# RT7258QW-break.net
KiCad netlist of a schematic drawn in EAGLE
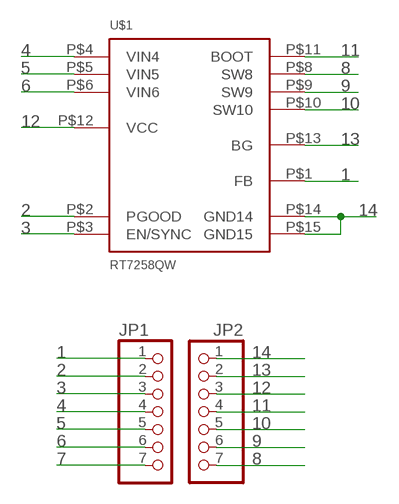
[diagram p0: schematic, sheet 1]

(export (version "E")
  (design (tool "Eeschema 10.0.6"))
  (components
    (comp (ref "JP1")
      (value "PINHD-1X7")
      (footprint "eagle-import:1X07")
      (libsource (lib "eagle-import") (part "PINHD-1X7"))
    )
    (comp (ref "JP2")
      (value "PINHD-1X7")
      (footprint "eagle-import:1X07")
      (libsource (lib "eagle-import") (part "PINHD-1X7"))
    )
    (comp (ref "U$1")
      (value "RT7258QW")
      (footprint "eagle-import:RT7258GQW")
      (libsource (lib "eagle-import") (part "RT7258QW"))
    )
  )
  (nets
    (net (code "1") (name "/1") (class "Default")
      (node (ref "JP1") (pin "1") (pinfunction "1_1") (pintype "passive"))
      (node (ref "U$1") (pin "P$1") (pinfunction "FB_P$1") (pintype "bidirectional"))
    )
    (net (code "2") (name "/2") (class "Default")
      (node (ref "JP1") (pin "2") (pinfunction "2_2") (pintype "passive"))
      (node (ref "U$1") (pin "P$2") (pinfunction "PGOOD_P$2") (pintype "bidirectional"))
    )
    (net (code "3") (name "/3") (class "Default")
      (node (ref "JP1") (pin "3") (pinfunction "3_3") (pintype "passive"))
      (node (ref "U$1") (pin "P$3") (pinfunction "EN/SYNC_P$3") (pintype "bidirectional"))
    )
    (net (code "4") (name "/4") (class "Default")
      (node (ref "JP1") (pin "4") (pinfunction "4_4") (pintype "passive"))
      (node (ref "U$1") (pin "P$4") (pinfunction "VIN4_P$4") (pintype "bidirectional"))
    )
    (net (code "5") (name "/5") (class "Default")
      (node (ref "JP1") (pin "5") (pinfunction "5_5") (pintype "passive"))
      (node (ref "U$1") (pin "P$5") (pinfunction "VIN5_P$5") (pintype "bidirectional"))
    )
    (net (code "6") (name "/6") (class "Default")
      (node (ref "JP1") (pin "6") (pinfunction "6_6") (pintype "passive"))
      (node (ref "U$1") (pin "P$6") (pinfunction "VIN6_P$6") (pintype "bidirectional"))
    )
    (net (code "7") (name "/7") (class "Default")
      (node (ref "JP1") (pin "7") (pinfunction "7_7") (pintype "passive"))
    )
    (net (code "8") (name "/8") (class "Default")
      (node (ref "JP2") (pin "7") (pinfunction "7_7") (pintype "passive"))
      (node (ref "U$1") (pin "P$8") (pinfunction "SW8_P$8") (pintype "bidirectional"))
    )
    (net (code "9") (name "/9") (class "Default")
      (node (ref "JP2") (pin "6") (pinfunction "6_6") (pintype "passive"))
      (node (ref "U$1") (pin "P$9") (pinfunction "SW9_P$9") (pintype "bidirectional"))
    )
    (net (code "10") (name "/10") (class "Default")
      (node (ref "JP2") (pin "5") (pinfunction "5_5") (pintype "passive"))
      (node (ref "U$1") (pin "P$10") (pinfunction "SW10_P$10") (pintype "bidirectional"))
    )
    (net (code "11") (name "/11") (class "Default")
      (node (ref "JP2") (pin "4") (pinfunction "4_4") (pintype "passive"))
      (node (ref "U$1") (pin "P$11") (pinfunction "BOOT_P$11") (pintype "bidirectional"))
    )
    (net (code "12") (name "/12") (class "Default")
      (node (ref "JP2") (pin "3") (pinfunction "3_3") (pintype "passive"))
      (node (ref "U$1") (pin "P$12") (pinfunction "VCC_P$12") (pintype "bidirectional"))
    )
    (net (code "13") (name "/13") (class "Default")
      (node (ref "JP2") (pin "2") (pinfunction "2_2") (pintype "passive"))
      (node (ref "U$1") (pin "P$13") (pinfunction "BG_P$13") (pintype "bidirectional"))
    )
    (net (code "14") (name "/14") (class "Default")
      (node (ref "JP2") (pin "1") (pinfunction "1_1") (pintype "passive"))
      (node (ref "U$1") (pin "P$14") (pinfunction "GND14_P$14") (pintype "bidirectional"))
      (node (ref "U$1") (pin "P$15") (pinfunction "GND15_P$15") (pintype "bidirectional"))
    )
  )
)
